# NDIR_SensorInterface.net
KiCad netlist of a schematic drawn in EAGLE
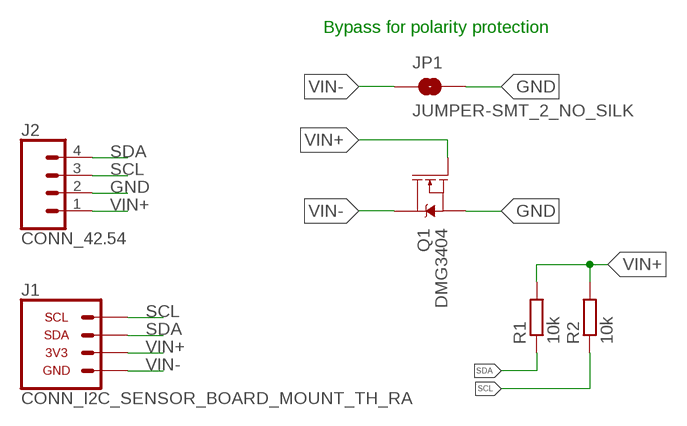
[diagram p0: schematic, sheet 1]

(export (version "E")
  (design (tool "Eeschema 10.0.6"))
  (components
    (comp (ref "J1")
      (value "CONN_I2C_SENSOR_BOARD_MOUNT_TH_RA")
      (footprint "eagle-import:CONEC_43-01204")
      (fields (field (name "MF") "Conec") (field (name "MPN") "43-01204"))
      (libsource (lib "eagle-import") (part "CONN_I2C_SENSOR_BOARD_MOUNT_TH_RA"))
    )
    (comp (ref "J2")
      (value "CONN_42.54")
      (footprint "eagle-import:1X04")
      (fields (field (name "MF") "Mill-Max") (field (name "MPN") "800-10-004-10-002000"))
      (libsource (lib "eagle-import") (part "CONN_42.54"))
    )
    (comp (ref "JP1")
      (value "JUMPER-SMT_2_NO_SILK")
      (footprint "eagle-import:SMT-JUMPER_2_NO_SILK")
      (libsource (lib "eagle-import") (part "JUMPER-SMT_2_NO_SILK"))
    )
    (comp (ref "Q1")
      (value "DMG3404")
      (footprint "eagle-import:SOT23-3")
      (fields (field (name "MF") "Diodes Incorporated") (field (name "MPN") "DMG3404L-7"))
      (libsource (lib "eagle-import") (part "MOSFET-NCH-DMG3404L"))
    )
    (comp (ref "R1")
      (value "10k")
      (footprint "eagle-import:R0603")
      (fields (field (name "MF") "Yageo") (field (name "MPN") "RC0603FR-0710KL"))
      (libsource (lib "eagle-import") (part "R-EU_R060310K"))
    )
    (comp (ref "R2")
      (value "10k")
      (footprint "eagle-import:R0603")
      (fields (field (name "MF") "Yageo") (field (name "MPN") "RC0603FR-0710KL"))
      (libsource (lib "eagle-import") (part "R-EU_R060310K"))
    )
  )
  (nets
    (net (code "1") (name "GND") (class "Default")
      (node (ref "J2") (pin "2") (pinfunction "2_2") (pintype "passive"))
      (node (ref "JP1") (pin "2") (pinfunction "2_2") (pintype "passive"))
      (node (ref "Q1") (pin "2") (pinfunction "S_2") (pintype "bidirectional"))
    )
    (net (code "2") (name "SCL") (class "Default")
      (node (ref "J1") (pin "3") (pinfunction "SCL_3") (pintype "passive"))
      (node (ref "J2") (pin "3") (pinfunction "3_3") (pintype "passive"))
      (node (ref "R2") (pin "1") (pinfunction "1_1") (pintype "passive"))
    )
    (net (code "3") (name "SDA") (class "Default")
      (node (ref "J1") (pin "1") (pinfunction "SDA_1") (pintype "passive"))
      (node (ref "J2") (pin "4") (pinfunction "4_4") (pintype "passive"))
      (node (ref "R1") (pin "1") (pinfunction "1_1") (pintype "passive"))
    )
    (net (code "4") (name "VIN+") (class "Default")
      (node (ref "J1") (pin "2") (pinfunction "3V3_2") (pintype "passive"))
      (node (ref "J2") (pin "1") (pinfunction "1_1") (pintype "passive"))
      (node (ref "Q1") (pin "1") (pinfunction "G_1") (pintype "bidirectional"))
      (node (ref "R1") (pin "2") (pinfunction "2_2") (pintype "passive"))
      (node (ref "R2") (pin "2") (pinfunction "2_2") (pintype "passive"))
    )
    (net (code "5") (name "VIN-") (class "Default")
      (node (ref "J1") (pin "4") (pinfunction "GND_4") (pintype "passive"))
      (node (ref "JP1") (pin "1") (pinfunction "1_1") (pintype "passive"))
      (node (ref "Q1") (pin "3") (pinfunction "D_3") (pintype "bidirectional"))
    )
  )
)
